# esp32camWithInfrared.net
KiCad netlist of a schematic drawn in EAGLE
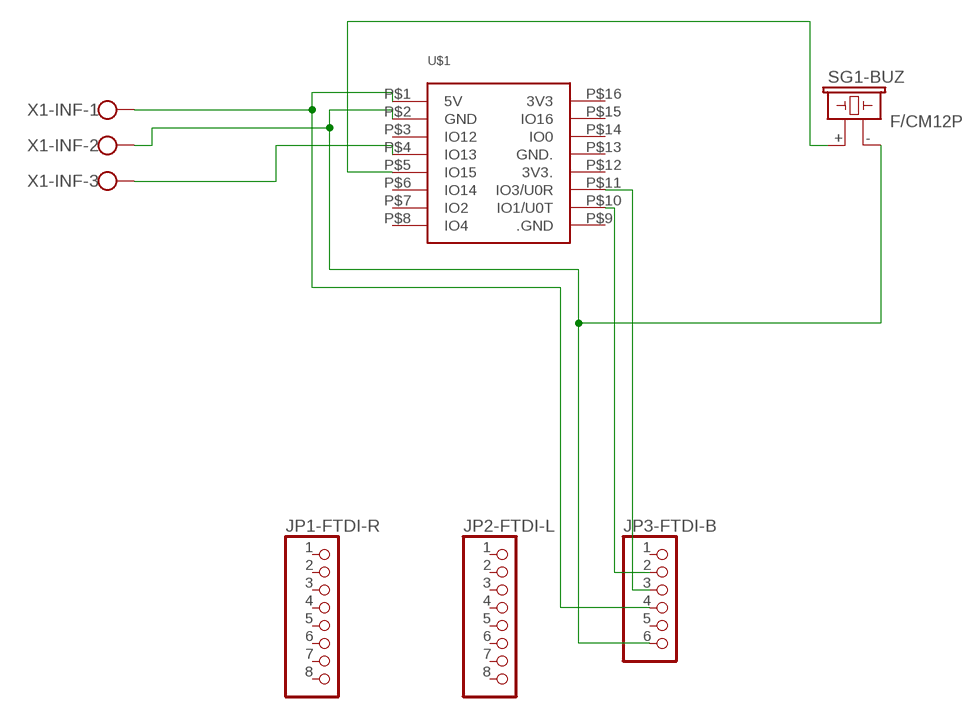
[diagram p0: schematic, sheet 1]

(export (version "E")
  (design (tool "Eeschema 10.0.6"))
  (components
    (comp (ref "JP1-FTDI-R")
      (value "PINHD-1X8")
      (footprint "eagle-import:1X08")
      (libsource (lib "eagle-import") (part "PINHD-1X8"))
    )
    (comp (ref "JP2-FTDI-L")
      (value "PINHD-1X8")
      (footprint "eagle-import:1X08")
      (libsource (lib "eagle-import") (part "PINHD-1X8"))
    )
    (comp (ref "JP3-FTDI-B")
      (value "PINHD-1X6")
      (footprint "eagle-import:1X06")
      (libsource (lib "eagle-import") (part "PINHD-1X6"))
    )
    (comp (ref "SG1-BUZ")
      (value "F/CM12P")
      (footprint "eagle-import:F_CM12P")
      (libsource (lib "eagle-import") (part "F/CM12P"))
    )
    (comp (ref "U$1")
      (value "ESP32-CAM")
      (footprint "eagle-import:ESP32-CAM")
      (fields (field (name "MF") "AI-Thinker"))
      (libsource (lib "eagle-import") (part "ESP32-CAM"))
    )
    (comp (ref "X1-INF")
      (value "W237-103")
      (footprint "eagle-import:W237-103")
      (fields (field (name "MPN") "237-103"))
      (libsource (lib "eagle-import") (part "W237-103"))
    )
  )
  (nets
    (net (code "1") (name "Net-(SG1-BUZ-1)") (class "Default")
      (node (ref "SG1-BUZ") (pin "+") (pinfunction "1_+") (pintype "passive"))
      (node (ref "U$1") (pin "P$5") (pinfunction "IO15_P$5") (pintype "bidirectional"))
    )
    (net (code "2") (name "Net-(SG1-BUZ-2)") (class "Default")
      (node (ref "JP3-FTDI-B") (pin "6") (pinfunction "6_6") (pintype "passive"))
      (node (ref "SG1-BUZ") (pin "-") (pinfunction "2_-") (pintype "passive"))
      (node (ref "U$1") (pin "P$2") (pinfunction "GND_P$2") (pintype "bidirectional"))
      (node (ref "X1-INF") (pin "2") (pinfunction "KL_2") (pintype "passive"))
    )
    (net (code "3") (name "Net-(U$1-5V)") (class "Default")
      (node (ref "JP3-FTDI-B") (pin "4") (pinfunction "4_4") (pintype "passive"))
      (node (ref "U$1") (pin "P$1") (pinfunction "5V_P$1") (pintype "bidirectional"))
      (node (ref "X1-INF") (pin "1") (pinfunction "KL_1") (pintype "passive"))
    )
    (net (code "4") (name "Net-(U$1-IO1{slash}U0T)") (class "Default")
      (node (ref "JP3-FTDI-B") (pin "2") (pinfunction "2_2") (pintype "passive"))
      (node (ref "U$1") (pin "P$10") (pinfunction "IO1/U0T_P$10") (pintype "bidirectional"))
    )
    (net (code "5") (name "Net-(U$1-IO3{slash}U0R)") (class "Default")
      (node (ref "JP3-FTDI-B") (pin "3") (pinfunction "3_3") (pintype "passive"))
      (node (ref "U$1") (pin "P$11") (pinfunction "IO3/U0R_P$11") (pintype "bidirectional"))
    )
    (net (code "6") (name "Net-(U$1-IO13)") (class "Default")
      (node (ref "U$1") (pin "P$4") (pinfunction "IO13_P$4") (pintype "bidirectional"))
      (node (ref "X1-INF") (pin "3") (pinfunction "KL_3") (pintype "passive"))
    )
    (net (code "7") (name "unconnected-(JP1-FTDI-R-Pad1)") (class "Default")
      (node (ref "JP1-FTDI-R") (pin "1") (pinfunction "1_1") (pintype "passive"))
    )
    (net (code "8") (name "unconnected-(JP1-FTDI-R-Pad2)") (class "Default")
      (node (ref "JP1-FTDI-R") (pin "2") (pinfunction "2_2") (pintype "passive"))
    )
    (net (code "9") (name "unconnected-(JP1-FTDI-R-Pad3)") (class "Default")
      (node (ref "JP1-FTDI-R") (pin "3") (pinfunction "3_3") (pintype "passive"))
    )
    (net (code "10") (name "unconnected-(JP1-FTDI-R-Pad4)") (class "Default")
      (node (ref "JP1-FTDI-R") (pin "4") (pinfunction "4_4") (pintype "passive"))
    )
    (net (code "11") (name "unconnected-(JP1-FTDI-R-Pad5)") (class "Default")
      (node (ref "JP1-FTDI-R") (pin "5") (pinfunction "5_5") (pintype "passive"))
    )
    (net (code "12") (name "unconnected-(JP1-FTDI-R-Pad6)") (class "Default")
      (node (ref "JP1-FTDI-R") (pin "6") (pinfunction "6_6") (pintype "passive"))
    )
    (net (code "13") (name "unconnected-(JP1-FTDI-R-Pad7)") (class "Default")
      (node (ref "JP1-FTDI-R") (pin "7") (pinfunction "7_7") (pintype "passive"))
    )
    (net (code "14") (name "unconnected-(JP1-FTDI-R-Pad8)") (class "Default")
      (node (ref "JP1-FTDI-R") (pin "8") (pinfunction "8_8") (pintype "passive"))
    )
    (net (code "15") (name "unconnected-(JP2-FTDI-L-Pad1)") (class "Default")
      (node (ref "JP2-FTDI-L") (pin "1") (pinfunction "1_1") (pintype "passive"))
    )
    (net (code "16") (name "unconnected-(JP2-FTDI-L-Pad2)") (class "Default")
      (node (ref "JP2-FTDI-L") (pin "2") (pinfunction "2_2") (pintype "passive"))
    )
    (net (code "17") (name "unconnected-(JP2-FTDI-L-Pad3)") (class "Default")
      (node (ref "JP2-FTDI-L") (pin "3") (pinfunction "3_3") (pintype "passive"))
    )
    (net (code "18") (name "unconnected-(JP2-FTDI-L-Pad4)") (class "Default")
      (node (ref "JP2-FTDI-L") (pin "4") (pinfunction "4_4") (pintype "passive"))
    )
    (net (code "19") (name "unconnected-(JP2-FTDI-L-Pad5)") (class "Default")
      (node (ref "JP2-FTDI-L") (pin "5") (pinfunction "5_5") (pintype "passive"))
    )
    (net (code "20") (name "unconnected-(JP2-FTDI-L-Pad6)") (class "Default")
      (node (ref "JP2-FTDI-L") (pin "6") (pinfunction "6_6") (pintype "passive"))
    )
    (net (code "21") (name "unconnected-(JP2-FTDI-L-Pad7)") (class "Default")
      (node (ref "JP2-FTDI-L") (pin "7") (pinfunction "7_7") (pintype "passive"))
    )
    (net (code "22") (name "unconnected-(JP2-FTDI-L-Pad8)") (class "Default")
      (node (ref "JP2-FTDI-L") (pin "8") (pinfunction "8_8") (pintype "passive"))
    )
    (net (code "23") (name "unconnected-(JP3-FTDI-B-Pad1)") (class "Default")
      (node (ref "JP3-FTDI-B") (pin "1") (pinfunction "1_1") (pintype "passive"))
    )
    (net (code "24") (name "unconnected-(JP3-FTDI-B-Pad5)") (class "Default")
      (node (ref "JP3-FTDI-B") (pin "5") (pinfunction "5_5") (pintype "passive"))
    )
    (net (code "25") (name "unconnected-(U$1-.GND-PadP$9)") (class "Default")
      (node (ref "U$1") (pin "P$9") (pinfunction ".GND_P$9") (pintype "bidirectional"))
    )
    (net (code "26") (name "unconnected-(U$1-3V3-PadP$16)") (class "Default")
      (node (ref "U$1") (pin "P$16") (pinfunction "3V3_P$16") (pintype "bidirectional"))
    )
    (net (code "27") (name "unconnected-(U$1-3V3.-PadP$12)") (class "Default")
      (node (ref "U$1") (pin "P$12") (pinfunction "3V3._P$12") (pintype "bidirectional"))
    )
    (net (code "28") (name "unconnected-(U$1-GND.-PadP$13)") (class "Default")
      (node (ref "U$1") (pin "P$13") (pinfunction "GND._P$13") (pintype "bidirectional"))
    )
    (net (code "29") (name "unconnected-(U$1-IO0-PadP$14)") (class "Default")
      (node (ref "U$1") (pin "P$14") (pinfunction "IO0_P$14") (pintype "bidirectional"))
    )
    (net (code "30") (name "unconnected-(U$1-IO2-PadP$7)") (class "Default")
      (node (ref "U$1") (pin "P$7") (pinfunction "IO2_P$7") (pintype "bidirectional"))
    )
    (net (code "31") (name "unconnected-(U$1-IO4-PadP$8)") (class "Default")
      (node (ref "U$1") (pin "P$8") (pinfunction "IO4_P$8") (pintype "bidirectional"))
    )
    (net (code "32") (name "unconnected-(U$1-IO12-PadP$3)") (class "Default")
      (node (ref "U$1") (pin "P$3") (pinfunction "IO12_P$3") (pintype "bidirectional"))
    )
    (net (code "33") (name "unconnected-(U$1-IO14-PadP$6)") (class "Default")
      (node (ref "U$1") (pin "P$6") (pinfunction "IO14_P$6") (pintype "bidirectional"))
    )
    (net (code "34") (name "unconnected-(U$1-IO16-PadP$15)") (class "Default")
      (node (ref "U$1") (pin "P$15") (pinfunction "IO16_P$15") (pintype "bidirectional"))
    )
  )
)
